# MCU.net
KiCad netlist of a schematic drawn in Altium Designer
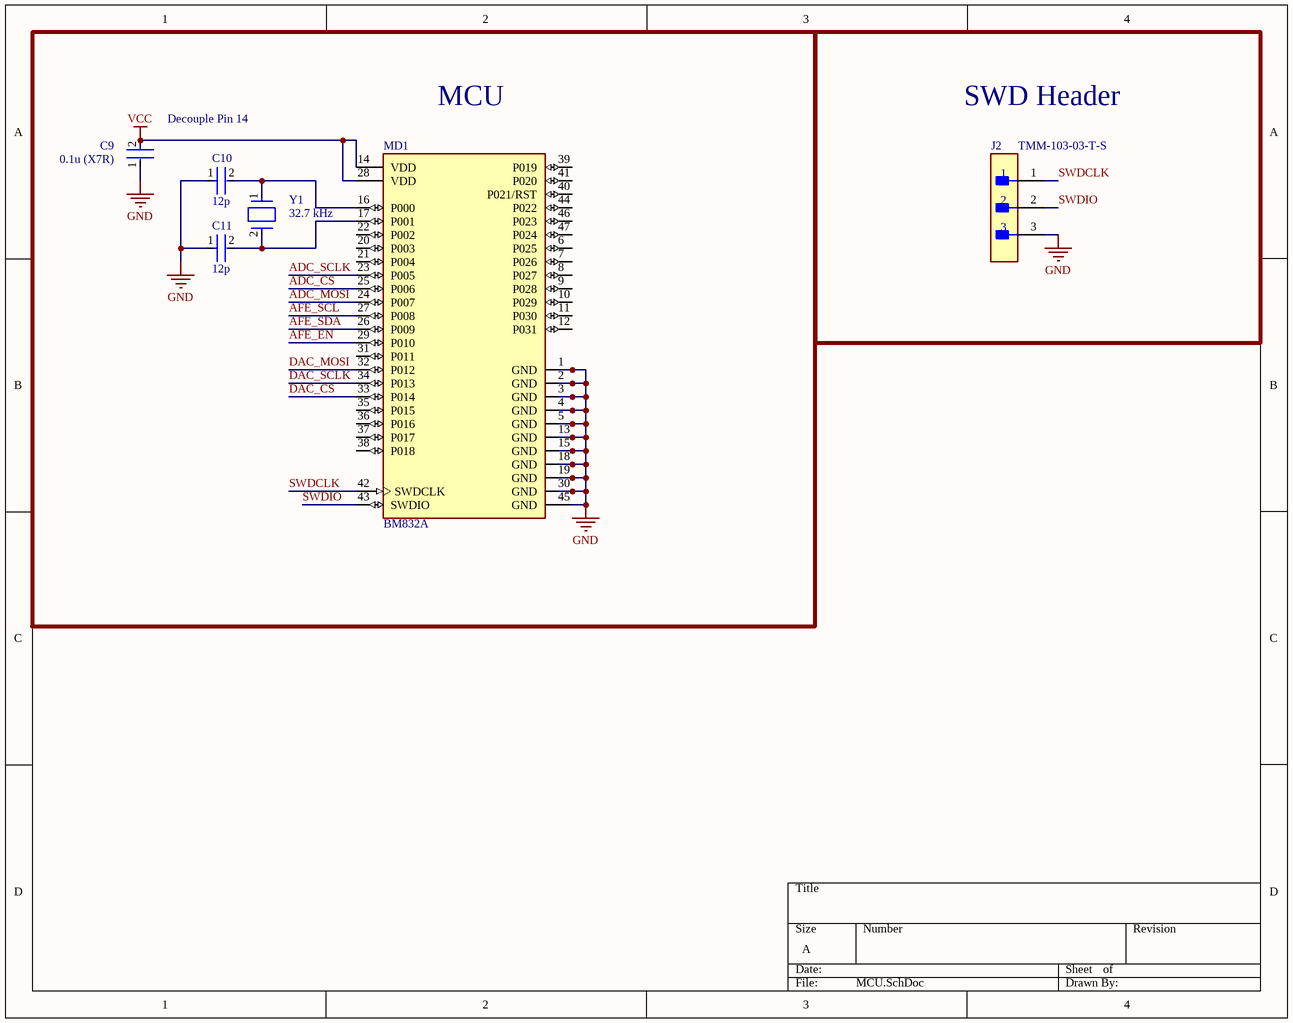
[diagram p0: MCU.SchDoc]

(export (version "E")
  (design (tool "Eeschema 10.0.6"))
  (components
    (comp (ref "C9")
      (value "0.1u (X7R)")
      (footprint "FP-GCJ188-0_2-IPC_C")
      (description "Cap Ceramic 0.1uF 50V X7R 10% Pad SMD 0603 Soft Termination +125°C Automotive T/R")
      (fields (field (name "TOLERANCE") "10%"))
      (libsource (lib "Altium Content Vault") (part "f23184f103b6ebe33a8c269c53dcba6"))
    )
    (comp (ref "C10")
      (value "12p")
      (footprint "FP-GCM188-0_1-IPC_B")
      (description "Ceramic Capacitor for Automotive 12pF  ±1% 100VDC C0G 0603 Paper T/R")
      (libsource (lib "Altium Content Vault") (part "02cd4be3c70576c341d710602a673aa"))
    )
    (comp (ref "C11")
      (value "12p")
      (footprint "FP-GCM188-0_1-IPC_B")
      (description "Ceramic Capacitor for Automotive 12pF  ±1% 100VDC C0G 0603 Paper T/R")
      (libsource (lib "Altium Content Vault") (part "02cd4be3c70576c341d710602a673aa"))
    )
    (comp (ref "J2")
      (value "TMM-103-03-T-S")
      (footprint "FP-TMM-103-03-T-S-MFG")
      (description "CONN HEADER VERT 3POS 2MM")
      (libsource (lib "Altium Content Vault") (part "0d3f023dd272f625e17a2be33dea85f"))
    )
    (comp (ref "MD1")
      (value "BM832A")
      (footprint "FP-BM832A-MFG")
      (description "RX TXRX MODULE BT PCB TRC SMD")
      (libsource (lib "Altium Content Vault") (part "ff9a6b7a189510e6265c2f568198abe"))
    )
    (comp (ref "Y1")
      (value "32.7 kHz")
      (footprint "FP-ECS-CDX-MFG")
      (description "CRYSTAL 32.7680KHZ 12.5PF SMD")
      (libsource (lib "Altium Content Vault") (part "99724985039315a44fd0d1401b84e49"))
    )
  )
  (nets
    (net (code "1") (name "/ADC_CS") (class "Default")
      (node (ref "MD1") (pin "25") (pinfunction "P006_25") (pintype "bidirectional"))
    )
    (net (code "2") (name "/ADC_MOSI") (class "Default")
      (node (ref "MD1") (pin "24") (pinfunction "P007_24") (pintype "bidirectional"))
    )
    (net (code "3") (name "/ADC_SCLK") (class "Default")
      (node (ref "MD1") (pin "23") (pinfunction "P005_23") (pintype "bidirectional"))
    )
    (net (code "4") (name "/AFE_EN") (class "Default")
      (node (ref "MD1") (pin "29") (pinfunction "P010_29") (pintype "bidirectional"))
    )
    (net (code "5") (name "/AFE_SCL") (class "Default")
      (node (ref "MD1") (pin "27") (pinfunction "P008_27") (pintype "bidirectional"))
    )
    (net (code "6") (name "/AFE_SDA") (class "Default")
      (node (ref "MD1") (pin "26") (pinfunction "P009_26") (pintype "bidirectional"))
    )
    (net (code "7") (name "/DAC_CS") (class "Default")
      (node (ref "MD1") (pin "33") (pinfunction "P014_33") (pintype "bidirectional"))
    )
    (net (code "8") (name "/DAC_MOSI") (class "Default")
      (node (ref "MD1") (pin "32") (pinfunction "P012_32") (pintype "bidirectional"))
    )
    (net (code "9") (name "/DAC_SCLK") (class "Default")
      (node (ref "MD1") (pin "34") (pinfunction "P013_34") (pintype "bidirectional"))
    )
    (net (code "10") (name "/SWDCLK") (class "Default")
      (node (ref "J2") (pin "1") (pinfunction "1_1") (pintype "passive"))
      (node (ref "MD1") (pin "42") (pinfunction "SWDCLK_42") (pintype "input"))
    )
    (net (code "11") (name "/SWDIO") (class "Default")
      (node (ref "J2") (pin "2") (pinfunction "2_2") (pintype "passive"))
      (node (ref "MD1") (pin "43") (pinfunction "SWDIO_43") (pintype "bidirectional"))
    )
    (net (code "12") (name "GND") (class "Default")
      (node (ref "C10") (pin "1") (pinfunction "1_1") (pintype "passive"))
      (node (ref "C11") (pin "1") (pinfunction "1_1") (pintype "passive"))
      (node (ref "C9") (pin "1") (pinfunction "1_1") (pintype "passive"))
      (node (ref "J2") (pin "3") (pinfunction "3_3") (pintype "passive"))
      (node (ref "MD1") (pin "1") (pinfunction "GND_1") (pintype "power_in"))
      (node (ref "MD1") (pin "13") (pinfunction "GND_13") (pintype "power_in"))
      (node (ref "MD1") (pin "15") (pinfunction "GND_15") (pintype "power_in"))
      (node (ref "MD1") (pin "18") (pinfunction "GND_18") (pintype "power_in"))
      (node (ref "MD1") (pin "19") (pinfunction "GND_19") (pintype "power_in"))
      (node (ref "MD1") (pin "2") (pinfunction "GND_2") (pintype "power_in"))
      (node (ref "MD1") (pin "3") (pinfunction "GND_3") (pintype "power_in"))
      (node (ref "MD1") (pin "30") (pinfunction "GND_30") (pintype "power_in"))
      (node (ref "MD1") (pin "4") (pinfunction "GND_4") (pintype "power_in"))
      (node (ref "MD1") (pin "45") (pinfunction "GND_45") (pintype "power_in"))
      (node (ref "MD1") (pin "5") (pinfunction "GND_5") (pintype "power_in"))
    )
    (net (code "13") (name "Net-(MD1-P000)") (class "Default")
      (node (ref "C10") (pin "2") (pinfunction "2_2") (pintype "passive"))
      (node (ref "MD1") (pin "16") (pinfunction "P000_16") (pintype "bidirectional"))
      (node (ref "Y1") (pin "1") (pinfunction "In/Out_1") (pintype "passive"))
    )
    (net (code "14") (name "Net-(MD1-P001)") (class "Default")
      (node (ref "C11") (pin "2") (pinfunction "2_2") (pintype "passive"))
      (node (ref "MD1") (pin "17") (pinfunction "P001_17") (pintype "bidirectional"))
      (node (ref "Y1") (pin "2") (pinfunction "Out/In_2") (pintype "passive"))
    )
    (net (code "15") (name "VCC") (class "Default")
      (node (ref "C9") (pin "2") (pinfunction "2_2") (pintype "passive"))
      (node (ref "MD1") (pin "14") (pinfunction "VDD_14") (pintype "power_in"))
      (node (ref "MD1") (pin "28") (pinfunction "VDD_28") (pintype "power_in"))
    )
    (net (code "16") (name "unconnected-(MD1-P002-Pad22)") (class "Default")
      (node (ref "MD1") (pin "22") (pinfunction "P002_22") (pintype "bidirectional"))
    )
    (net (code "17") (name "unconnected-(MD1-P003-Pad20)") (class "Default")
      (node (ref "MD1") (pin "20") (pinfunction "P003_20") (pintype "bidirectional"))
    )
    (net (code "18") (name "unconnected-(MD1-P004-Pad21)") (class "Default")
      (node (ref "MD1") (pin "21") (pinfunction "P004_21") (pintype "bidirectional"))
    )
    (net (code "19") (name "unconnected-(MD1-P011-Pad31)") (class "Default")
      (node (ref "MD1") (pin "31") (pinfunction "P011_31") (pintype "bidirectional"))
    )
    (net (code "20") (name "unconnected-(MD1-P015-Pad35)") (class "Default")
      (node (ref "MD1") (pin "35") (pinfunction "P015_35") (pintype "bidirectional"))
    )
    (net (code "21") (name "unconnected-(MD1-P016-Pad36)") (class "Default")
      (node (ref "MD1") (pin "36") (pinfunction "P016_36") (pintype "bidirectional"))
    )
    (net (code "22") (name "unconnected-(MD1-P017-Pad37)") (class "Default")
      (node (ref "MD1") (pin "37") (pinfunction "P017_37") (pintype "bidirectional"))
    )
    (net (code "23") (name "unconnected-(MD1-P018-Pad38)") (class "Default")
      (node (ref "MD1") (pin "38") (pinfunction "P018_38") (pintype "bidirectional"))
    )
    (net (code "24") (name "unconnected-(MD1-P019-Pad39)") (class "Default")
      (node (ref "MD1") (pin "39") (pinfunction "P019_39") (pintype "bidirectional"))
    )
    (net (code "25") (name "unconnected-(MD1-P020-Pad41)") (class "Default")
      (node (ref "MD1") (pin "41") (pinfunction "P020_41") (pintype "bidirectional"))
    )
    (net (code "26") (name "unconnected-(MD1-P021{slash}RST-Pad40)") (class "Default")
      (node (ref "MD1") (pin "40") (pinfunction "P021/RST_40") (pintype "bidirectional"))
    )
    (net (code "27") (name "unconnected-(MD1-P022-Pad44)") (class "Default")
      (node (ref "MD1") (pin "44") (pinfunction "P022_44") (pintype "bidirectional"))
    )
    (net (code "28") (name "unconnected-(MD1-P023-Pad46)") (class "Default")
      (node (ref "MD1") (pin "46") (pinfunction "P023_46") (pintype "bidirectional"))
    )
    (net (code "29") (name "unconnected-(MD1-P024-Pad47)") (class "Default")
      (node (ref "MD1") (pin "47") (pinfunction "P024_47") (pintype "bidirectional"))
    )
    (net (code "30") (name "unconnected-(MD1-P025-Pad6)") (class "Default")
      (node (ref "MD1") (pin "6") (pinfunction "P025_6") (pintype "bidirectional"))
    )
    (net (code "31") (name "unconnected-(MD1-P026-Pad7)") (class "Default")
      (node (ref "MD1") (pin "7") (pinfunction "P026_7") (pintype "bidirectional"))
    )
    (net (code "32") (name "unconnected-(MD1-P027-Pad8)") (class "Default")
      (node (ref "MD1") (pin "8") (pinfunction "P027_8") (pintype "bidirectional"))
    )
    (net (code "33") (name "unconnected-(MD1-P028-Pad9)") (class "Default")
      (node (ref "MD1") (pin "9") (pinfunction "P028_9") (pintype "bidirectional"))
    )
    (net (code "34") (name "unconnected-(MD1-P029-Pad10)") (class "Default")
      (node (ref "MD1") (pin "10") (pinfunction "P029_10") (pintype "bidirectional"))
    )
    (net (code "35") (name "unconnected-(MD1-P030-Pad11)") (class "Default")
      (node (ref "MD1") (pin "11") (pinfunction "P030_11") (pintype "bidirectional"))
    )
    (net (code "36") (name "unconnected-(MD1-P031-Pad12)") (class "Default")
      (node (ref "MD1") (pin "12") (pinfunction "P031_12") (pintype "bidirectional"))
    )
  )
)
